# FPGA_SPI_interface.net
KiCad netlist of a schematic drawn in Altium Designer
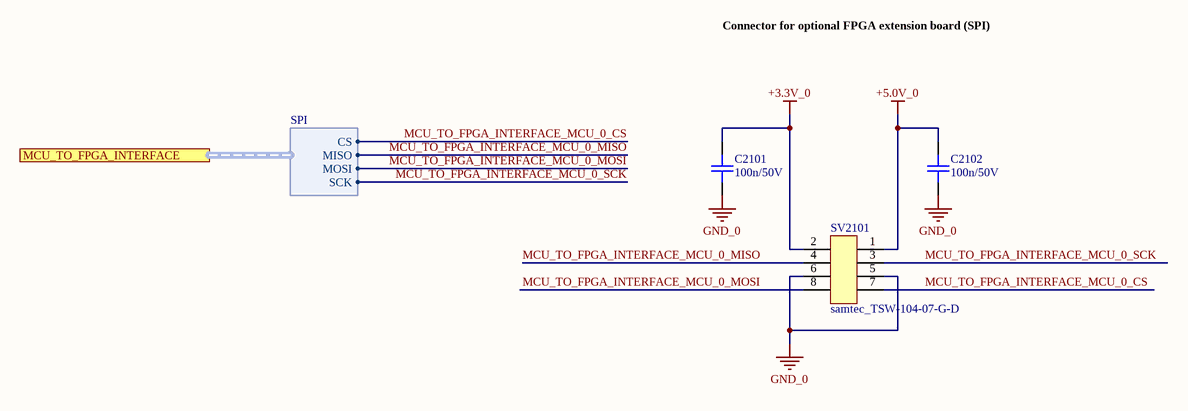
[diagram p0: FPGA_SPI_interface.SchDoc]

(export (version "E")
  (design (tool "Eeschema 10.0.6"))
  (components
    (comp (ref "C2101")
      (value "100n/50V")
      (footprint "CAPC1608X08N")
      (description "MLCC")
      (fields (field (name "PART NUMBER") "gen_C_ceramic_100n_50V_X7R_0603"))
      (libsource (lib "OE750") (part "C"))
    )
    (comp (ref "C2102")
      (value "100n/50V")
      (footprint "CAPC1608X08N")
      (description "MLCC")
      (fields (field (name "PART NUMBER") "gen_C_ceramic_100n_50V_X7R_0603"))
      (libsource (lib "OE750") (part "C"))
    )
    (comp (ref "SV2101")
      (value "samtec_TSW-104-07-G-D")
      (footprint "Pinheader_2.54_2x4")
      (description "Board-To-Board Connector, Vertical, 2.54 mm, 8 Contacts, Header, TSW Series, Through Hole, 2 Rows")
      (fields (field (name "MANUFACTURER") "Samtec"))
      (libsource (lib "OE750") (part "X2x4"))
    )
  )
  (nets
    (net (code "2") (name "+3.3V_0") (class "Default")
      (node (ref "C2101") (pin "2") (pinfunction "2_2") (pintype "passive"))
      (node (ref "SV2101") (pin "2") (pintype "passive"))
    )
    (net (code "3") (name "+5.0V_0") (class "Default")
      (node (ref "C2102") (pin "1") (pinfunction "1_1") (pintype "passive"))
      (node (ref "SV2101") (pin "1") (pintype "passive"))
    )
    (net (code "4") (name "/MCU_TO_FPGA_INTERFACE_MCU_0_CS") (class "Default")
      (node (ref "SV2101") (pin "7") (pintype "passive"))
    )
    (net (code "5") (name "/MCU_TO_FPGA_INTERFACE_MCU_0_MISO") (class "Default")
      (node (ref "SV2101") (pin "4") (pintype "passive"))
    )
    (net (code "6") (name "/MCU_TO_FPGA_INTERFACE_MCU_0_MOSI") (class "Default")
      (node (ref "SV2101") (pin "8") (pintype "passive"))
    )
    (net (code "7") (name "/MCU_TO_FPGA_INTERFACE_MCU_0_SCK") (class "Default")
      (node (ref "SV2101") (pin "3") (pintype "passive"))
    )
    (net (code "9") (name "GND_0") (class "Default")
      (node (ref "C2101") (pin "1") (pinfunction "1_1") (pintype "passive"))
      (node (ref "C2102") (pin "2") (pinfunction "2_2") (pintype "passive"))
      (node (ref "SV2101") (pin "5") (pintype "passive"))
      (node (ref "SV2101") (pin "6") (pintype "passive"))
    )
  )
)
